# STM.net
KiCad netlist of a schematic drawn in Altium Designer
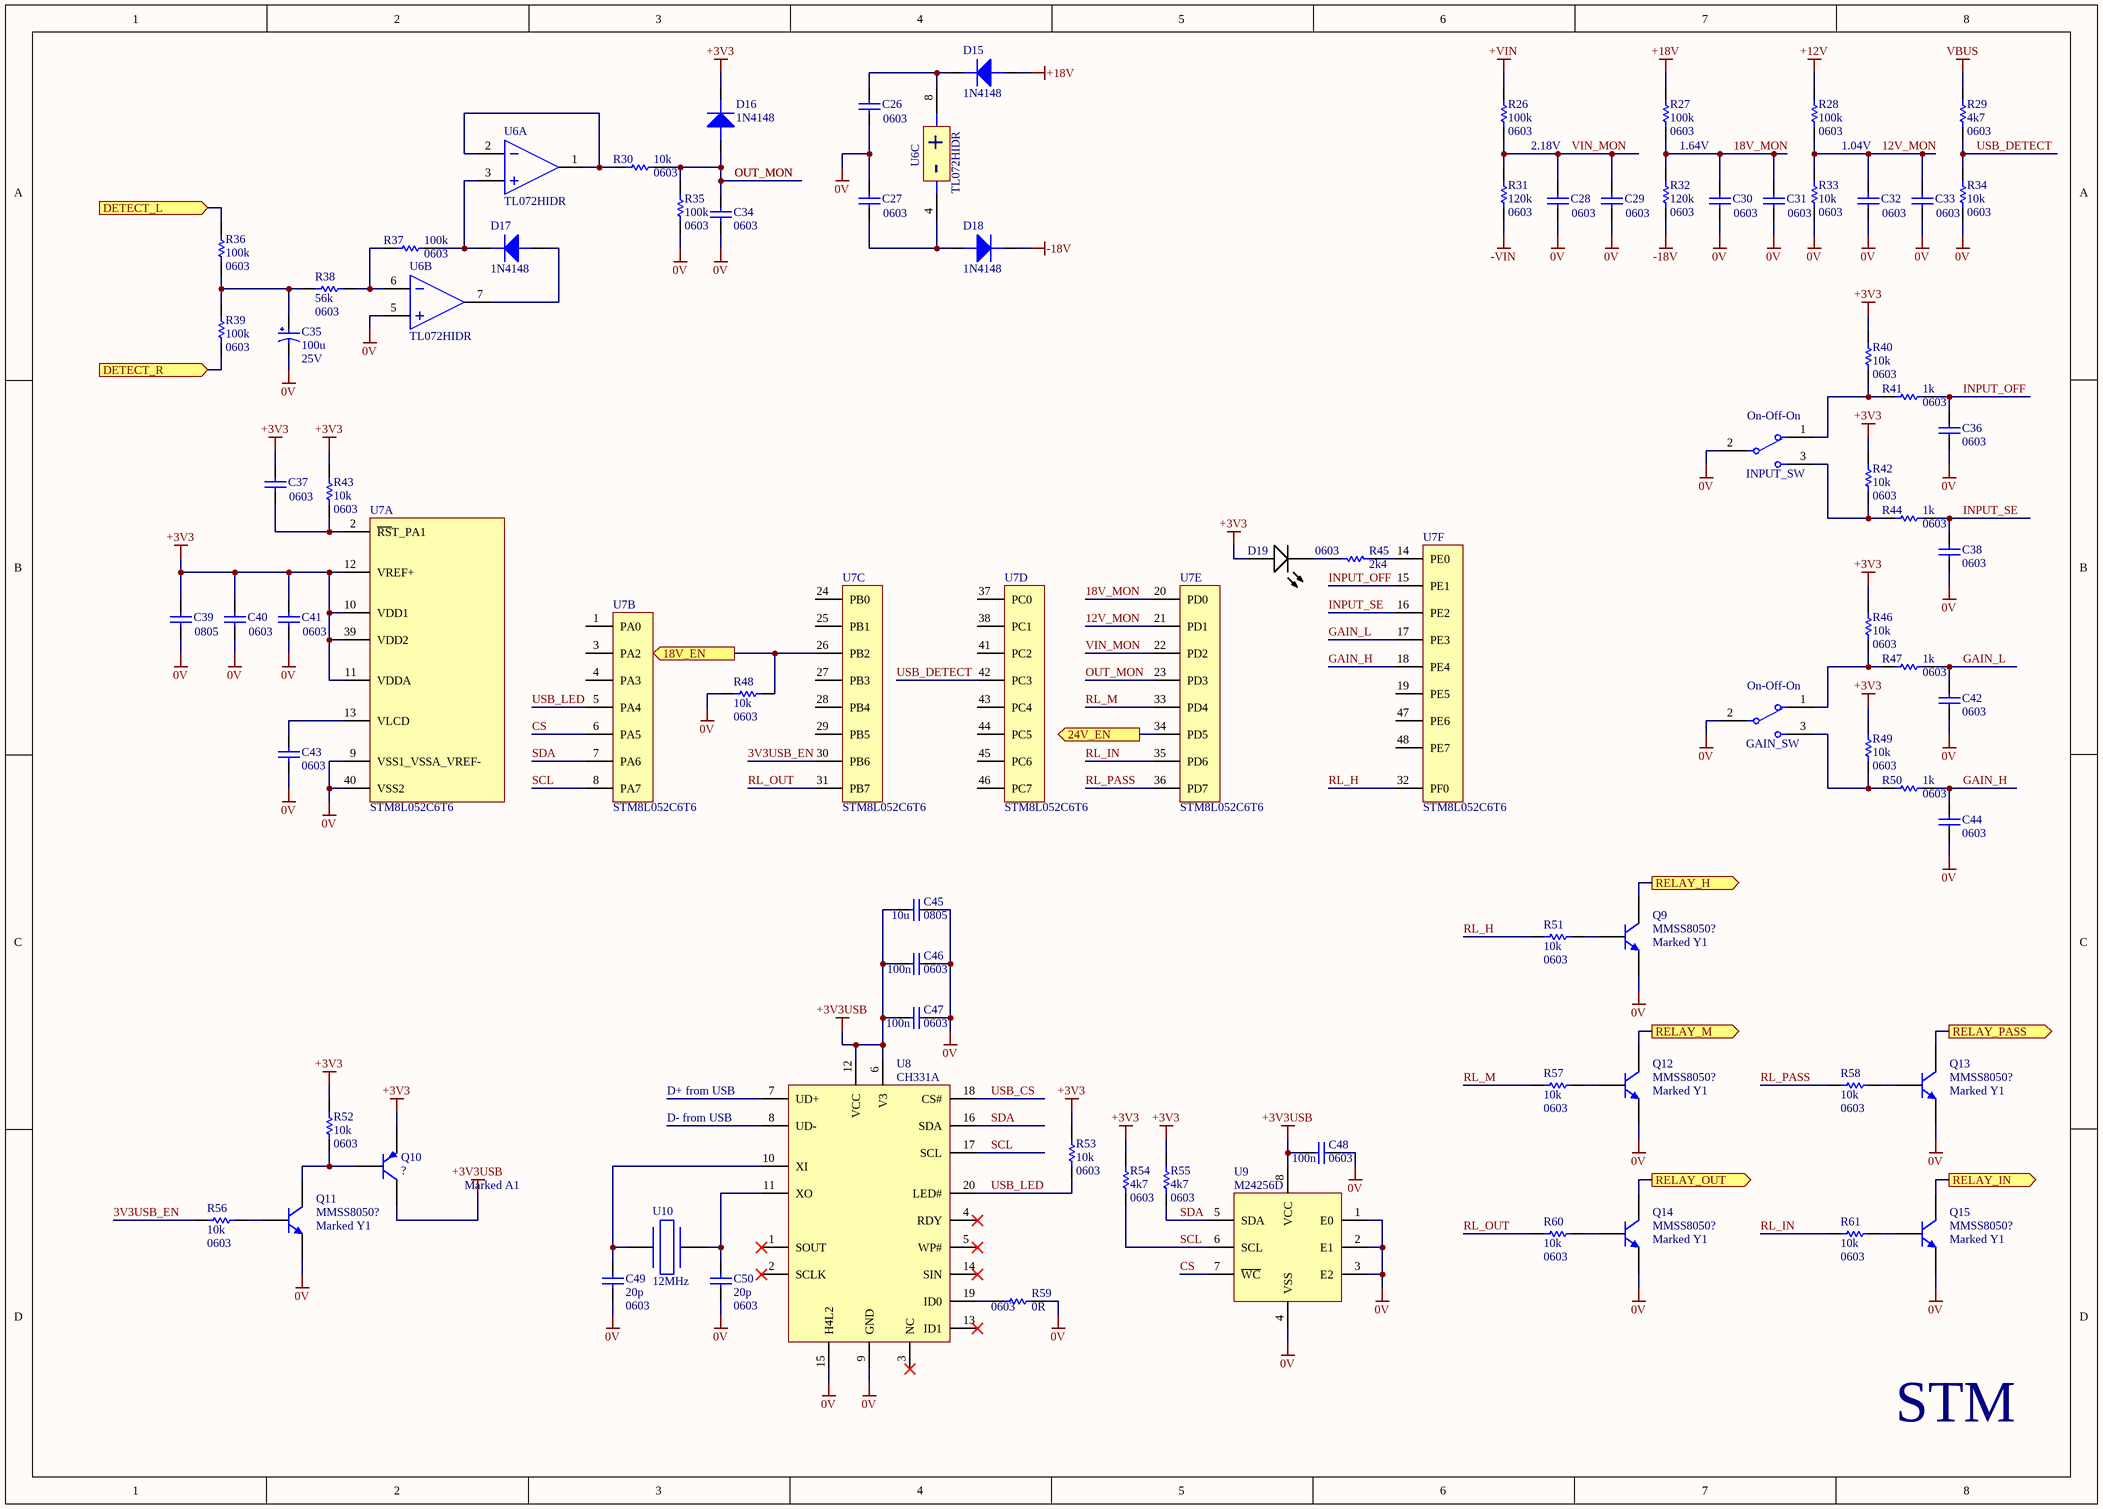
[diagram p0: STM.SchDoc]

(export (version "E")
  (design (tool "Eeschema 10.0.6"))
  (components
    (comp (ref "C26")
      (value "C_MLCC_0603")
      (footprint "CAPC1608X09N")
      (description "Generic MLCC 0603 Non Polarized Capacitor")
      (fields (field (name "MANUFACTURER") "Generic") (field (name "PACKAGE") "0603"))
      (libsource (lib "Topping_L50") (part "C_MLCC_0603"))
    )
    (comp (ref "C27")
      (value "C_MLCC_0603")
      (footprint "CAPC1608X09N")
      (description "Generic MLCC 0603 Non Polarized Capacitor")
      (fields (field (name "MANUFACTURER") "Generic") (field (name "PACKAGE") "0603"))
      (libsource (lib "Topping_L50") (part "C_MLCC_0603"))
    )
    (comp (ref "C28")
      (value "C_MLCC_0603")
      (footprint "CAPC1608X09N")
      (description "Generic MLCC 0603 Non Polarized Capacitor")
      (fields (field (name "MANUFACTURER") "Generic") (field (name "PACKAGE") "0603"))
      (libsource (lib "Topping_L50") (part "C_MLCC_0603"))
    )
    (comp (ref "C29")
      (value "C_MLCC_0603")
      (footprint "CAPC1608X09N")
      (description "Generic MLCC 0603 Non Polarized Capacitor")
      (fields (field (name "MANUFACTURER") "Generic") (field (name "PACKAGE") "0603"))
      (libsource (lib "Topping_L50") (part "C_MLCC_0603"))
    )
    (comp (ref "C30")
      (value "C_MLCC_0603")
      (footprint "CAPC1608X09N")
      (description "Generic MLCC 0603 Non Polarized Capacitor")
      (fields (field (name "MANUFACTURER") "Generic") (field (name "PACKAGE") "0603"))
      (libsource (lib "Topping_L50") (part "C_MLCC_0603"))
    )
    (comp (ref "C31")
      (value "C_MLCC_0603")
      (footprint "CAPC1608X09N")
      (description "Generic MLCC 0603 Non Polarized Capacitor")
      (fields (field (name "MANUFACTURER") "Generic") (field (name "PACKAGE") "0603"))
      (libsource (lib "Topping_L50") (part "C_MLCC_0603"))
    )
    (comp (ref "C32")
      (value "C_MLCC_0603")
      (footprint "CAPC1608X09N")
      (description "Generic MLCC 0603 Non Polarized Capacitor")
      (fields (field (name "MANUFACTURER") "Generic") (field (name "PACKAGE") "0603"))
      (libsource (lib "Topping_L50") (part "C_MLCC_0603"))
    )
    (comp (ref "C33")
      (value "C_MLCC_0603")
      (footprint "CAPC1608X09N")
      (description "Generic MLCC 0603 Non Polarized Capacitor")
      (fields (field (name "MANUFACTURER") "Generic") (field (name "PACKAGE") "0603"))
      (libsource (lib "Topping_L50") (part "C_MLCC_0603"))
    )
    (comp (ref "C34")
      (value "C_MLCC_0603")
      (footprint "CAPC1608X09N")
      (description "Generic MLCC 0603 Non Polarized Capacitor")
      (fields (field (name "MANUFACTURER") "Generic") (field (name "PACKAGE") "0603"))
      (libsource (lib "Topping_L50") (part "C_MLCC_0603"))
    )
    (comp (ref "C35")
      (value "100u")
      (footprint "CAPAE13X20")
      (description "Alum. Electrolytic Cap 2200µF 16V 13mm Radial WCAP-ATLL; Lifetime 7000h +105°C")
      (fields
        (field (name "MANUFACTURER") "Würth Elektronik")
        (field (name "TOLERANCE") "20%")
        (field (name "NOTES") "25V")
      )
      (libsource (lib "Topping_L50") (part "860160378038"))
    )
    (comp (ref "C36")
      (value "C_MLCC_0603")
      (footprint "CAPC1608X09N")
      (description "Generic MLCC 0603 Non Polarized Capacitor")
      (fields (field (name "MANUFACTURER") "Generic") (field (name "PACKAGE") "0603"))
      (libsource (lib "Topping_L50") (part "C_MLCC_0603"))
    )
    (comp (ref "C37")
      (value "C_MLCC_0603")
      (footprint "CAPC1608X09N")
      (description "Generic MLCC 0603 Non Polarized Capacitor")
      (fields (field (name "MANUFACTURER") "Generic") (field (name "PACKAGE") "0603"))
      (libsource (lib "Topping_L50") (part "C_MLCC_0603"))
    )
    (comp (ref "C38")
      (value "C_MLCC_0603")
      (footprint "CAPC1608X09N")
      (description "Generic MLCC 0603 Non Polarized Capacitor")
      (fields (field (name "MANUFACTURER") "Generic") (field (name "PACKAGE") "0603"))
      (libsource (lib "Topping_L50") (part "C_MLCC_0603"))
    )
    (comp (ref "C39")
      (value "C_MLCC_0805")
      (footprint "CAPC2012X14N")
      (description "Generic MLCC 0805 Non Polarized Capacitor")
      (fields (field (name "MANUFACTURER") "Generic") (field (name "PACKAGE") "0805"))
      (libsource (lib "Topping_L50") (part "C_MLCC_0805"))
    )
    (comp (ref "C40")
      (value "C_MLCC_0603")
      (footprint "CAPC1608X09N")
      (description "Generic MLCC 0603 Non Polarized Capacitor")
      (fields (field (name "MANUFACTURER") "Generic") (field (name "PACKAGE") "0603"))
      (libsource (lib "Topping_L50") (part "C_MLCC_0603"))
    )
    (comp (ref "C41")
      (value "C_MLCC_0603")
      (footprint "CAPC1608X09N")
      (description "Generic MLCC 0603 Non Polarized Capacitor")
      (fields (field (name "MANUFACTURER") "Generic") (field (name "PACKAGE") "0603"))
      (libsource (lib "Topping_L50") (part "C_MLCC_0603"))
    )
    (comp (ref "C42")
      (value "C_MLCC_0603")
      (footprint "CAPC1608X09N")
      (description "Generic MLCC 0603 Non Polarized Capacitor")
      (fields (field (name "MANUFACTURER") "Generic") (field (name "PACKAGE") "0603"))
      (libsource (lib "Topping_L50") (part "C_MLCC_0603"))
    )
    (comp (ref "C43")
      (value "C_MLCC_0603")
      (footprint "CAPC1608X09N")
      (description "Generic MLCC 0603 Non Polarized Capacitor")
      (fields (field (name "MANUFACTURER") "Generic") (field (name "PACKAGE") "0603"))
      (libsource (lib "Topping_L50") (part "C_MLCC_0603"))
    )
    (comp (ref "C44")
      (value "C_MLCC_0603")
      (footprint "CAPC1608X09N")
      (description "Generic MLCC 0603 Non Polarized Capacitor")
      (fields (field (name "MANUFACTURER") "Generic") (field (name "PACKAGE") "0603"))
      (libsource (lib "Topping_L50") (part "C_MLCC_0603"))
    )
    (comp (ref "C45")
      (value "10u")
      (footprint "CAPC2012X14N")
      (description "Generic MLCC 0805 Non Polarized Capacitor")
      (fields
        (field (name "MANUFACTURER") "Generic")
        (field (name "PACKAGE") "0805")
        (field (name "Comment") "C_MLCC_0805")
      )
      (libsource (lib "Topping_L50") (part "C_MLCC_0805"))
    )
    (comp (ref "C46")
      (value "100n")
      (footprint "CAPC1608X09N")
      (description "Generic MLCC 0603 Non Polarized Capacitor")
      (fields
        (field (name "MANUFACTURER") "Generic")
        (field (name "PACKAGE") "0603")
        (field (name "Comment") "C_MLCC_0603")
      )
      (libsource (lib "Topping_L50") (part "C_MLCC_0603"))
    )
    (comp (ref "C47")
      (value "100n")
      (footprint "CAPC1608X09N")
      (description "Generic MLCC 0603 Non Polarized Capacitor")
      (fields
        (field (name "MANUFACTURER") "Generic")
        (field (name "PACKAGE") "0603")
        (field (name "Comment") "C_MLCC_0603")
      )
      (libsource (lib "Topping_L50") (part "C_MLCC_0603"))
    )
    (comp (ref "C48")
      (value "100n")
      (footprint "CAPC1608X09N")
      (description "Generic MLCC 0603 Non Polarized Capacitor")
      (fields
        (field (name "MANUFACTURER") "Generic")
        (field (name "PACKAGE") "0603")
        (field (name "Comment") "C_MLCC_0603")
      )
      (libsource (lib "Topping_L50") (part "C_MLCC_0603"))
    )
    (comp (ref "C49")
      (value "20p")
      (footprint "CAPC1608X09N")
      (description "Generic MLCC 0603 Non Polarized Capacitor")
      (fields
        (field (name "MANUFACTURER") "Generic")
        (field (name "PACKAGE") "0603")
        (field (name "Comment") "C_MLCC_0603")
      )
      (libsource (lib "Topping_L50") (part "C_MLCC_0603"))
    )
    (comp (ref "C50")
      (value "20p")
      (footprint "CAPC1608X09N")
      (description "Generic MLCC 0603 Non Polarized Capacitor")
      (fields
        (field (name "MANUFACTURER") "Generic")
        (field (name "PACKAGE") "0603")
        (field (name "Comment") "C_MLCC_0603")
      )
      (libsource (lib "Topping_L50") (part "C_MLCC_0603"))
    )
    (comp (ref "D15")
      (value "1N4148")
      (description "Generic small signal diode")
      (fields (field (name "MANUFACTURER") "Generic") (field (name "MANUFACTURER PART NUMBER") "BAT48ZFILM"))
      (libsource (lib "Topping_L50") (part "1N4148"))
    )
    (comp (ref "D16")
      (value "1N4148")
      (description "Generic small signal diode")
      (fields (field (name "MANUFACTURER") "Generic") (field (name "MANUFACTURER PART NUMBER") "BAT48ZFILM"))
      (libsource (lib "Topping_L50") (part "1N4148"))
    )
    (comp (ref "D17")
      (value "1N4148")
      (description "Generic small signal diode")
      (fields (field (name "MANUFACTURER") "Generic") (field (name "MANUFACTURER PART NUMBER") "BAT48ZFILM"))
      (libsource (lib "Topping_L50") (part "1N4148"))
    )
    (comp (ref "D18")
      (value "1N4148")
      (description "Generic small signal diode")
      (fields (field (name "MANUFACTURER") "Generic") (field (name "MANUFACTURER PART NUMBER") "BAT48ZFILM"))
      (libsource (lib "Topping_L50") (part "1N4148"))
    )
    (comp (ref "D19")
      (value "LED_TH_3mm_RED")
      (description "Generic Through Hole 3mm Red Led")
      (fields (field (name "MANUFACTURER") "Generic"))
      (libsource (lib "Topping_L50") (part "LED_TH_3mm_RED"))
    )
    (comp (ref "GAIN_SW")
      (value "On-Off-On")
      (description "Mini Toggle Switch 1M Series SPDT ON-ON Short Lever PC Through-Hole")
      (fields (field (name "MANUFACTURER") "Dailywell") (field (name "Comment") "1MS1T2B1M2QES"))
      (libsource (lib "Topping_L50") (part "1MS1T2B1M2QES"))
    )
    (comp (ref "INPUT_SW")
      (value "On-Off-On")
      (description "Mini Toggle Switch 1M Series SPDT ON-ON Short Lever PC Through-Hole")
      (fields (field (name "MANUFACTURER") "Dailywell") (field (name "Comment") "1MS1T2B1M2QES"))
      (libsource (lib "Topping_L50") (part "1MS1T2B1M2QES"))
    )
    (comp (ref "Q9")
      (value "MMSS8050?")
      (footprint "SOT95P230X110-3N")
      (description "NPN General-Purpose\r\nAmplifier")
      (fields (field (name "MANUFACTURER") "On Semi") (field (name "MANUFACTURER PART NUMBER") "MMBT3904VL"))
      (libsource (lib "Topping_L50") (part "MMBT5551"))
    )
    (comp (ref "Q10")
      (value "?")
      (footprint "SOT95P230X110-3N")
      (description "PNP Epitaxial Silicon Transistor")
      (fields (field (name "MANUFACTURER") "MCC") (field (name "MANUFACTURER PART NUMBER") "MMBT3904VL"))
      (libsource (lib "Topping_L50") (part "MMBT5401"))
    )
    (comp (ref "Q11")
      (value "MMSS8050?")
      (footprint "SOT95P230X110-3N")
      (description "NPN General-Purpose\r\nAmplifier")
      (fields (field (name "MANUFACTURER") "On Semi") (field (name "MANUFACTURER PART NUMBER") "MMBT3904VL"))
      (libsource (lib "Topping_L50") (part "MMBT5551"))
    )
    (comp (ref "Q12")
      (value "MMSS8050?")
      (footprint "SOT95P230X110-3N")
      (description "NPN General-Purpose\r\nAmplifier")
      (fields (field (name "MANUFACTURER") "On Semi") (field (name "MANUFACTURER PART NUMBER") "MMBT3904VL"))
      (libsource (lib "Topping_L50") (part "MMBT5551"))
    )
    (comp (ref "Q13")
      (value "MMSS8050?")
      (footprint "SOT95P230X110-3N")
      (description "NPN General-Purpose\r\nAmplifier")
      (fields (field (name "MANUFACTURER") "On Semi") (field (name "MANUFACTURER PART NUMBER") "MMBT3904VL"))
      (libsource (lib "Topping_L50") (part "MMBT5551"))
    )
    (comp (ref "Q14")
      (value "MMSS8050?")
      (footprint "SOT95P230X110-3N")
      (description "NPN General-Purpose\r\nAmplifier")
      (fields (field (name "MANUFACTURER") "On Semi") (field (name "MANUFACTURER PART NUMBER") "MMBT3904VL"))
      (libsource (lib "Topping_L50") (part "MMBT5551"))
    )
    (comp (ref "Q15")
      (value "MMSS8050?")
      (footprint "SOT95P230X110-3N")
      (description "NPN General-Purpose\r\nAmplifier")
      (fields (field (name "MANUFACTURER") "On Semi") (field (name "MANUFACTURER PART NUMBER") "MMBT3904VL"))
      (libsource (lib "Topping_L50") (part "MMBT5551"))
    )
    (comp (ref "R26")
      (value "100k")
      (footprint "RESC1608X06N")
      (description "Generic 0603 Single Resistor")
      (fields
        (field (name "MANUFACTURER") "Generic")
        (field (name "PACKAGE") "0603")
        (field (name "Comment") "R")
      )
      (libsource (lib "Topping_L50") (part "R_0603"))
    )
    (comp (ref "R27")
      (value "100k")
      (footprint "RESC1608X06N")
      (description "Generic 0603 Single Resistor")
      (fields
        (field (name "MANUFACTURER") "Generic")
        (field (name "PACKAGE") "0603")
        (field (name "Comment") "R")
      )
      (libsource (lib "Topping_L50") (part "R_0603"))
    )
    (comp (ref "R28")
      (value "100k")
      (footprint "RESC1608X06N")
      (description "Generic 0603 Single Resistor")
      (fields
        (field (name "MANUFACTURER") "Generic")
        (field (name "PACKAGE") "0603")
        (field (name "Comment") "R")
      )
      (libsource (lib "Topping_L50") (part "R_0603"))
    )
    (comp (ref "R29")
      (value "4k7")
      (footprint "RESC1608X06N")
      (description "Generic 0603 Single Resistor")
      (fields
        (field (name "MANUFACTURER") "Generic")
        (field (name "PACKAGE") "0603")
        (field (name "Comment") "R")
      )
      (libsource (lib "Topping_L50") (part "R_0603"))
    )
    (comp (ref "R30")
      (value "10k")
      (footprint "RESC1608X06N")
      (description "Generic 0603 Single Resistor")
      (fields
        (field (name "MANUFACTURER") "Generic")
        (field (name "PACKAGE") "0603")
        (field (name "Comment") "R")
      )
      (libsource (lib "Topping_L50") (part "R_0603"))
    )
    (comp (ref "R31")
      (value "120k")
      (footprint "RESC1608X06N")
      (description "Generic 0603 Single Resistor")
      (fields
        (field (name "MANUFACTURER") "Generic")
        (field (name "PACKAGE") "0603")
        (field (name "Comment") "R")
      )
      (libsource (lib "Topping_L50") (part "R_0603"))
    )
    (comp (ref "R32")
      (value "120k")
      (footprint "RESC1608X06N")
      (description "Generic 0603 Single Resistor")
      (fields
        (field (name "MANUFACTURER") "Generic")
        (field (name "PACKAGE") "0603")
        (field (name "Comment") "R")
      )
      (libsource (lib "Topping_L50") (part "R_0603"))
    )
    (comp (ref "R33")
      (value "10k")
      (footprint "RESC1608X06N")
      (description "Generic 0603 Single Resistor")
      (fields
        (field (name "MANUFACTURER") "Generic")
        (field (name "PACKAGE") "0603")
        (field (name "Comment") "R")
      )
      (libsource (lib "Topping_L50") (part "R_0603"))
    )
    (comp (ref "R34")
      (value "10k")
      (footprint "RESC1608X06N")
      (description "Generic 0603 Single Resistor")
      (fields
        (field (name "MANUFACTURER") "Generic")
        (field (name "PACKAGE") "0603")
        (field (name "Comment") "R")
      )
      (libsource (lib "Topping_L50") (part "R_0603"))
    )
    (comp (ref "R35")
      (value "100k")
      (footprint "RESC1608X06N")
      (description "Generic 0603 Single Resistor")
      (fields
        (field (name "MANUFACTURER") "Generic")
        (field (name "PACKAGE") "0603")
        (field (name "Comment") "R")
      )
      (libsource (lib "Topping_L50") (part "R_0603"))
    )
    (comp (ref "R36")
      (value "100k")
      (footprint "RESC1608X06N")
      (description "Generic 0603 Single Resistor")
      (fields
        (field (name "MANUFACTURER") "Generic")
        (field (name "PACKAGE") "0603")
        (field (name "Comment") "R")
      )
      (libsource (lib "Topping_L50") (part "R_0603"))
    )
    (comp (ref "R37")
      (value "100k")
      (footprint "RESC1608X06N")
      (description "Generic 0603 Single Resistor")
      (fields
        (field (name "MANUFACTURER") "Generic")
        (field (name "PACKAGE") "0603")
        (field (name "Comment") "R")
      )
      (libsource (lib "Topping_L50") (part "R_0603"))
    )
    (comp (ref "R38")
      (value "56k")
      (footprint "RESC1608X06N")
      (description "Generic 0603 Single Resistor")
      (fields
        (field (name "MANUFACTURER") "Generic")
        (field (name "PACKAGE") "0603")
        (field (name "Comment") "R")
      )
      (libsource (lib "Topping_L50") (part "R_0603"))
    )
    (comp (ref "R39")
      (value "100k")
      (footprint "RESC1608X06N")
      (description "Generic 0603 Single Resistor")
      (fields
        (field (name "MANUFACTURER") "Generic")
        (field (name "PACKAGE") "0603")
        (field (name "Comment") "R")
      )
      (libsource (lib "Topping_L50") (part "R_0603"))
    )
    (comp (ref "R40")
      (value "10k")
      (footprint "RESC1608X06N")
      (description "Generic 0603 Single Resistor")
      (fields
        (field (name "MANUFACTURER") "Generic")
        (field (name "PACKAGE") "0603")
        (field (name "Comment") "R")
      )
      (libsource (lib "Topping_L50") (part "R_0603"))
    )
    (comp (ref "R41")
      (value "1k")
      (footprint "RESC1608X06N")
      (description "Generic 0603 Single Resistor")
      (fields
        (field (name "MANUFACTURER") "Generic")
        (field (name "PACKAGE") "0603")
        (field (name "Comment") "R")
      )
      (libsource (lib "Topping_L50") (part "R_0603"))
    )
    (comp (ref "R42")
      (value "10k")
      (footprint "RESC1608X06N")
      (description "Generic 0603 Single Resistor")
      (fields
        (field (name "MANUFACTURER") "Generic")
        (field (name "PACKAGE") "0603")
        (field (name "Comment") "R")
      )
      (libsource (lib "Topping_L50") (part "R_0603"))
    )
    (comp (ref "R43")
      (value "10k")
      (footprint "RESC1608X06N")
      (description "Generic 0603 Single Resistor")
      (fields
        (field (name "MANUFACTURER") "Generic")
        (field (name "PACKAGE") "0603")
        (field (name "Comment") "R")
      )
      (libsource (lib "Topping_L50") (part "R_0603"))
    )
    (comp (ref "R44")
      (value "1k")
      (footprint "RESC1608X06N")
      (description "Generic 0603 Single Resistor")
      (fields
        (field (name "MANUFACTURER") "Generic")
        (field (name "PACKAGE") "0603")
        (field (name "Comment") "R")
      )
      (libsource (lib "Topping_L50") (part "R_0603"))
    )
    (comp (ref "R45")
      (value "2k4")
      (footprint "RESC1608X06N")
      (description "Generic 0603 Single Resistor")
      (fields
        (field (name "MANUFACTURER") "Generic")
        (field (name "PACKAGE") "0603")
        (field (name "Comment") "R")
      )
      (libsource (lib "Topping_L50") (part "R_0603"))
    )
    (comp (ref "R46")
      (value "10k")
      (footprint "RESC1608X06N")
      (description "Generic 0603 Single Resistor")
      (fields
        (field (name "MANUFACTURER") "Generic")
        (field (name "PACKAGE") "0603")
        (field (name "Comment") "R")
      )
      (libsource (lib "Topping_L50") (part "R_0603"))
    )
    (comp (ref "R47")
      (value "1k")
      (footprint "RESC1608X06N")
      (description "Generic 0603 Single Resistor")
      (fields
        (field (name "MANUFACTURER") "Generic")
        (field (name "PACKAGE") "0603")
        (field (name "Comment") "R")
      )
      (libsource (lib "Topping_L50") (part "R_0603"))
    )
    (comp (ref "R48")
      (value "10k")
      (footprint "RESC1608X06N")
      (description "Generic 0603 Single Resistor")
      (fields
        (field (name "MANUFACTURER") "Generic")
        (field (name "PACKAGE") "0603")
        (field (name "Comment") "R")
      )
      (libsource (lib "Topping_L50") (part "R_0603"))
    )
    (comp (ref "R49")
      (value "10k")
      (footprint "RESC1608X06N")
      (description "Generic 0603 Single Resistor")
      (fields
        (field (name "MANUFACTURER") "Generic")
        (field (name "PACKAGE") "0603")
        (field (name "Comment") "R")
      )
      (libsource (lib "Topping_L50") (part "R_0603"))
    )
    (comp (ref "R50")
      (value "1k")
      (footprint "RESC1608X06N")
      (description "Generic 0603 Single Resistor")
      (fields
        (field (name "MANUFACTURER") "Generic")
        (field (name "PACKAGE") "0603")
        (field (name "Comment") "R")
      )
      (libsource (lib "Topping_L50") (part "R_0603"))
    )
    (comp (ref "R51")
      (value "10k")
      (footprint "RESC1608X06N")
      (description "Generic 0603 Single Resistor")
      (fields
        (field (name "MANUFACTURER") "Generic")
        (field (name "PACKAGE") "0603")
        (field (name "Comment") "R")
      )
      (libsource (lib "Topping_L50") (part "R_0603"))
    )
    (comp (ref "R52")
      (value "10k")
      (footprint "RESC1608X06N")
      (description "Generic 0603 Single Resistor")
      (fields
        (field (name "MANUFACTURER") "Generic")
        (field (name "PACKAGE") "0603")
        (field (name "Comment") "R")
      )
      (libsource (lib "Topping_L50") (part "R_0603"))
    )
    (comp (ref "R53")
      (value "10k")
      (footprint "RESC1608X06N")
      (description "Generic 0603 Single Resistor")
      (fields
        (field (name "MANUFACTURER") "Generic")
        (field (name "PACKAGE") "0603")
        (field (name "Comment") "R")
      )
      (libsource (lib "Topping_L50") (part "R_0603"))
    )
    (comp (ref "R54")
      (value "4k7")
      (footprint "RESC1608X06N")
      (description "Generic 0603 Single Resistor")
      (fields
        (field (name "MANUFACTURER") "Generic")
        (field (name "PACKAGE") "0603")
        (field (name "Comment") "R")
      )
      (libsource (lib "Topping_L50") (part "R_0603"))
    )
    (comp (ref "R55")
      (value "4k7")
      (footprint "RESC1608X06N")
      (description "Generic 0603 Single Resistor")
      (fields
        (field (name "MANUFACTURER") "Generic")
        (field (name "PACKAGE") "0603")
        (field (name "Comment") "R")
      )
      (libsource (lib "Topping_L50") (part "R_0603"))
    )
    (comp (ref "R56")
      (value "10k")
      (footprint "RESC1608X06N")
      (description "Generic 0603 Single Resistor")
      (fields
        (field (name "MANUFACTURER") "Generic")
        (field (name "PACKAGE") "0603")
        (field (name "Comment") "R")
      )
      (libsource (lib "Topping_L50") (part "R_0603"))
    )
    (comp (ref "R57")
      (value "10k")
      (footprint "RESC1608X06N")
      (description "Generic 0603 Single Resistor")
      (fields
        (field (name "MANUFACTURER") "Generic")
        (field (name "PACKAGE") "0603")
        (field (name "Comment") "R")
      )
      (libsource (lib "Topping_L50") (part "R_0603"))
    )
    (comp (ref "R58")
      (value "10k")
      (footprint "RESC1608X06N")
      (description "Generic 0603 Single Resistor")
      (fields
        (field (name "MANUFACTURER") "Generic")
        (field (name "PACKAGE") "0603")
        (field (name "Comment") "R")
      )
      (libsource (lib "Topping_L50") (part "R_0603"))
    )
    (comp (ref "R59")
      (value "0R")
      (footprint "RESC1608X06N")
      (description "Generic 0603 Single Resistor")
      (fields
        (field (name "MANUFACTURER") "Generic")
        (field (name "PACKAGE") "0603")
        (field (name "Comment") "R")
      )
      (libsource (lib "Topping_L50") (part "R_0603"))
    )
    (comp (ref "R60")
      (value "10k")
      (footprint "RESC1608X06N")
      (description "Generic 0603 Single Resistor")
      (fields
        (field (name "MANUFACTURER") "Generic")
        (field (name "PACKAGE") "0603")
        (field (name "Comment") "R")
      )
      (libsource (lib "Topping_L50") (part "R_0603"))
    )
    (comp (ref "R61")
      (value "10k")
      (footprint "RESC1608X06N")
      (description "Generic 0603 Single Resistor")
      (fields
        (field (name "MANUFACTURER") "Generic")
        (field (name "PACKAGE") "0603")
        (field (name "Comment") "R")
      )
      (libsource (lib "Topping_L50") (part "R_0603"))
    )
    (comp (ref "U6")
      (value "TL072HIDR")
      (footprint "SOIC127P600X175-8L")
      (description "Operational Amplifiers - Op Amps Dual Low Noise Op Amp")
      (fields (field (name "MANUFACTURER") "Texas Instruments"))
      (libsource (lib "Topping_L50") (part "TL072HIDR"))
    )
    (comp (ref "U7")
      (value "STM8L052C6T6")
      (footprint "CQFP50P900X900X160-48N")
      (fields (field (name "MANUFACTURER") "ST Microelectronics"))
      (libsource (lib "Topping_L50") (part "STM8L052C6T6"))
    )
    (comp (ref "U8")
      (value "CH331A")
      (footprint "TSOP65P640X120-20N")
      (description "USB 2.0 SSOP-20-208mil USB Converters ROHS")
      (fields (field (name "MANUFACTURER") "WCH"))
      (libsource (lib "Topping_L50") (part "CH331A"))
    )
    (comp (ref "U9")
      (value "M24256D")
      (footprint "SOIC127P600X175-8L")
      (description "256-Kbit serial I²C bus EEPROM")
      (fields (field (name "MANUFACTURER") "ST Microelectronics"))
      (libsource (lib "Topping_L50") (part "M24256D"))
    )
    (comp (ref "U10")
      (value "12MHz")
      (description "Generic Xtal")
      (libsource (lib "Topping_L50") (part "Xtal"))
    )
  )
  (nets
    (net (code "1") (name "+3V3") (class "Default")
      (node (ref "C37") (pin "1") (pinfunction "1_1") (pintype "passive"))
      (node (ref "C39") (pin "2") (pinfunction "2_2") (pintype "passive"))
      (node (ref "C40") (pin "1") (pinfunction "1_1") (pintype "passive"))
      (node (ref "C41") (pin "1") (pinfunction "1_1") (pintype "passive"))
      (node (ref "D16") (pin "K") (pinfunction "K_K") (pintype "passive"))
      (node (ref "D19") (pin "A") (pinfunction "A_A") (pintype "passive"))
      (node (ref "Q10") (pin "E") (pinfunction "E_E") (pintype "passive"))
      (node (ref "R40") (pin "1") (pinfunction "1_1") (pintype "passive"))
      (node (ref "R42") (pin "2") (pinfunction "2_2") (pintype "passive"))
      (node (ref "R43") (pin "2") (pinfunction "2_2") (pintype "passive"))
      (node (ref "R46") (pin "1") (pinfunction "1_1") (pintype "passive"))
      (node (ref "R49") (pin "2") (pinfunction "2_2") (pintype "passive"))
      (node (ref "R52") (pin "2") (pinfunction "2_2") (pintype "passive"))
      (node (ref "R53") (pin "2") (pinfunction "2_2") (pintype "passive"))
      (node (ref "R54") (pin "2") (pinfunction "2_2") (pintype "passive"))
      (node (ref "R55") (pin "2") (pinfunction "2_2") (pintype "passive"))
      (node (ref "U7") (pin "10") (pinfunction "VDD1_10") (pintype "passive"))
      (node (ref "U7") (pin "11") (pinfunction "VDDA_11") (pintype "passive"))
      (node (ref "U7") (pin "12") (pinfunction "VREF+_12") (pintype "passive"))
      (node (ref "U7") (pin "39") (pinfunction "VDD2_39") (pintype "passive"))
    )
    (net (code "2") (name "+3V3USB") (class "Default")
      (node (ref "C45") (pin "2") (pinfunction "2_2") (pintype "passive"))
      (node (ref "C46") (pin "2") (pinfunction "2_2") (pintype "passive"))
      (node (ref "C47") (pin "2") (pinfunction "2_2") (pintype "passive"))
      (node (ref "C48") (pin "2") (pinfunction "2_2") (pintype "passive"))
      (node (ref "Q10") (pin "C") (pinfunction "C_C") (pintype "passive"))
      (node (ref "U8") (pin "12") (pinfunction "VCC_12") (pintype "passive"))
      (node (ref "U8") (pin "6") (pinfunction "V3_6") (pintype "passive"))
      (node (ref "U9") (pin "8") (pinfunction "VCC_8") (pintype "passive"))
    )
    (net (code "3") (name "+12V") (class "Default")
      (node (ref "R28") (pin "2") (pinfunction "2_2") (pintype "passive"))
    )
    (net (code "4") (name "+18V") (class "Default")
      (node (ref "D15") (pin "A") (pinfunction "A_A") (pintype "passive"))
      (node (ref "R27") (pin "2") (pinfunction "2_2") (pintype "passive"))
    )
    (net (code "5") (name "+VIN") (class "Default")
      (node (ref "R26") (pin "2") (pinfunction "2_2") (pintype "passive"))
    )
    (net (code "6") (name "-18V") (class "Default")
      (node (ref "D18") (pin "K") (pinfunction "K_K") (pintype "passive"))
      (node (ref "R32") (pin "1") (pinfunction "1_1") (pintype "passive"))
    )
    (net (code "7") (name "-VIN") (class "Default")
      (node (ref "R31") (pin "1") (pinfunction "1_1") (pintype "passive"))
    )
    (net (code "8") (name "/3V3USB_EN") (class "Default")
      (node (ref "R56") (pin "1") (pinfunction "1_1") (pintype "passive"))
      (node (ref "U7") (pin "30") (pinfunction "PB6_30") (pintype "passive"))
    )
    (net (code "9") (name "/12V_MON") (class "Default")
      (node (ref "C32") (pin "2") (pinfunction "2_2") (pintype "passive"))
      (node (ref "C33") (pin "2") (pinfunction "2_2") (pintype "passive"))
      (node (ref "R28") (pin "1") (pinfunction "1_1") (pintype "passive"))
      (node (ref "R33") (pin "2") (pinfunction "2_2") (pintype "passive"))
      (node (ref "U7") (pin "21") (pinfunction "PD1_21") (pintype "passive"))
    )
    (net (code "10") (name "/18V_EN") (class "Default")
      (node (ref "R48") (pin "2") (pinfunction "2_2") (pintype "passive"))
      (node (ref "U7") (pin "26") (pinfunction "PB2_26") (pintype "passive"))
    )
    (net (code "11") (name "/18V_MON") (class "Default")
      (node (ref "C30") (pin "2") (pinfunction "2_2") (pintype "passive"))
      (node (ref "C31") (pin "2") (pinfunction "2_2") (pintype "passive"))
      (node (ref "R27") (pin "1") (pinfunction "1_1") (pintype "passive"))
      (node (ref "R32") (pin "2") (pinfunction "2_2") (pintype "passive"))
      (node (ref "U7") (pin "20") (pinfunction "PD0_20") (pintype "passive"))
    )
    (net (code "12") (name "/24V_EN") (class "Default")
      (node (ref "U7") (pin "34") (pinfunction "PD5_34") (pintype "passive"))
    )
    (net (code "13") (name "/CS") (class "Default")
      (node (ref "U7") (pin "6") (pinfunction "PA5_6") (pintype "passive"))
      (node (ref "U9") (pin "7") (pinfunction "~{WC}_7") (pintype "passive"))
    )
    (net (code "14") (name "/DETECT_L") (class "Default")
      (node (ref "R36") (pin "1") (pinfunction "1_1") (pintype "passive"))
    )
    (net (code "15") (name "/DETECT_R") (class "Default")
      (node (ref "R39") (pin "2") (pinfunction "2_2") (pintype "passive"))
    )
    (net (code "16") (name "/GAIN_H") (class "Default")
      (node (ref "C44") (pin "2") (pinfunction "2_2") (pintype "passive"))
      (node (ref "R50") (pin "2") (pinfunction "2_2") (pintype "passive"))
      (node (ref "U7") (pin "18") (pinfunction "PE4_18") (pintype "passive"))
    )
    (net (code "17") (name "/GAIN_L") (class "Default")
      (node (ref "C42") (pin "2") (pinfunction "2_2") (pintype "passive"))
      (node (ref "R47") (pin "2") (pinfunction "2_2") (pintype "passive"))
      (node (ref "U7") (pin "17") (pinfunction "PE3_17") (pintype "passive"))
    )
    (net (code "18") (name "/INPUT_OFF") (class "Default")
      (node (ref "C36") (pin "2") (pinfunction "2_2") (pintype "passive"))
      (node (ref "R41") (pin "2") (pinfunction "2_2") (pintype "passive"))
      (node (ref "U7") (pin "15") (pinfunction "PE1_15") (pintype "passive"))
    )
    (net (code "19") (name "/INPUT_SE") (class "Default")
      (node (ref "C38") (pin "2") (pinfunction "2_2") (pintype "passive"))
      (node (ref "R44") (pin "2") (pinfunction "2_2") (pintype "passive"))
      (node (ref "U7") (pin "16") (pinfunction "PE2_16") (pintype "passive"))
    )
    (net (code "20") (name "/OUT_MON") (class "Default")
      (node (ref "C34") (pin "2") (pinfunction "2_2") (pintype "passive"))
      (node (ref "D16") (pin "A") (pinfunction "A_A") (pintype "passive"))
      (node (ref "R30") (pin "2") (pinfunction "2_2") (pintype "passive"))
      (node (ref "R35") (pin "2") (pinfunction "2_2") (pintype "passive"))
      (node (ref "U7") (pin "23") (pinfunction "PD3_23") (pintype "passive"))
    )
    (net (code "21") (name "/RELAY_H") (class "Default")
      (node (ref "Q9") (pin "C") (pinfunction "C_C") (pintype "passive"))
    )
    (net (code "22") (name "/RELAY_IN") (class "Default")
      (node (ref "Q15") (pin "C") (pinfunction "C_C") (pintype "passive"))
    )
    (net (code "23") (name "/RELAY_M") (class "Default")
      (node (ref "Q12") (pin "C") (pinfunction "C_C") (pintype "passive"))
    )
    (net (code "24") (name "/RELAY_OUT") (class "Default")
      (node (ref "Q14") (pin "C") (pinfunction "C_C") (pintype "passive"))
    )
    (net (code "25") (name "/RELAY_PASS") (class "Default")
      (node (ref "Q13") (pin "C") (pinfunction "C_C") (pintype "passive"))
    )
    (net (code "26") (name "/RL_H") (class "Default")
      (node (ref "R51") (pin "1") (pinfunction "1_1") (pintype "passive"))
      (node (ref "U7") (pin "32") (pinfunction "PF0_32") (pintype "passive"))
    )
    (net (code "27") (name "/RL_IN") (class "Default")
      (node (ref "R61") (pin "1") (pinfunction "1_1") (pintype "passive"))
      (node (ref "U7") (pin "35") (pinfunction "PD6_35") (pintype "passive"))
    )
    (net (code "28") (name "/RL_M") (class "Default")
      (node (ref "R57") (pin "1") (pinfunction "1_1") (pintype "passive"))
      (node (ref "U7") (pin "33") (pinfunction "PD4_33") (pintype "passive"))
    )
    (net (code "29") (name "/RL_OUT") (class "Default")
      (node (ref "R60") (pin "1") (pinfunction "1_1") (pintype "passive"))
      (node (ref "U7") (pin "31") (pinfunction "PB7_31") (pintype "passive"))
    )
    (net (code "30") (name "/RL_PASS") (class "Default")
      (node (ref "R58") (pin "1") (pinfunction "1_1") (pintype "passive"))
      (node (ref "U7") (pin "36") (pinfunction "PD7_36") (pintype "passive"))
    )
    (net (code "31") (name "/SCL") (class "Default")
      (node (ref "R54") (pin "1") (pinfunction "1_1") (pintype "passive"))
      (node (ref "U7") (pin "8") (pinfunction "PA7_8") (pintype "passive"))
      (node (ref "U8") (pin "17") (pinfunction "SCL_17") (pintype "passive"))
      (node (ref "U9") (pin "6") (pinfunction "SCL_6") (pintype "passive"))
    )
    (net (code "32") (name "/SDA") (class "Default")
      (node (ref "R55") (pin "1") (pinfunction "1_1") (pintype "passive"))
      (node (ref "U7") (pin "7") (pinfunction "PA6_7") (pintype "passive"))
      (node (ref "U8") (pin "16") (pinfunction "SDA_16") (pintype "passive"))
      (node (ref "U9") (pin "5") (pinfunction "SDA_5") (pintype "passive"))
    )
    (net (code "33") (name "/USB_CS") (class "Default")
      (node (ref "U8") (pin "18") (pinfunction "CS#_18") (pintype "passive"))
    )
    (net (code "34") (name "/USB_DETECT") (class "Default")
      (node (ref "R29") (pin "1") (pinfunction "1_1") (pintype "passive"))
      (node (ref "R34") (pin "2") (pinfunction "2_2") (pintype "passive"))
      (node (ref "U7") (pin "42") (pinfunction "PC3_42") (pintype "passive"))
    )
    (net (code "35") (name "/USB_LED") (class "Default")
      (node (ref "R53") (pin "1") (pinfunction "1_1") (pintype "passive"))
      (node (ref "U7") (pin "5") (pinfunction "PA4_5") (pintype "passive"))
      (node (ref "U8") (pin "20") (pinfunction "LED#_20") (pintype "passive"))
    )
    (net (code "36") (name "/VIN_MON") (class "Default")
      (node (ref "C28") (pin "2") (pinfunction "2_2") (pintype "passive"))
      (node (ref "C29") (pin "2") (pinfunction "2_2") (pintype "passive"))
      (node (ref "R26") (pin "1") (pinfunction "1_1") (pintype "passive"))
      (node (ref "R31") (pin "2") (pinfunction "2_2") (pintype "passive"))
      (node (ref "U7") (pin "22") (pinfunction "PD2_22") (pintype "passive"))
    )
    (net (code "37") (name "0V") (class "Default")
      (node (ref "C26") (pin "1") (pinfunction "1_1") (pintype "passive"))
      (node (ref "C27") (pin "2") (pinfunction "2_2") (pintype "passive"))
      (node (ref "C28") (pin "1") (pinfunction "1_1") (pintype "passive"))
      (node (ref "C29") (pin "1") (pinfunction "1_1") (pintype "passive"))
      (node (ref "C30") (pin "1") (pinfunction "1_1") (pintype "passive"))
      (node (ref "C31") (pin "1") (pinfunction "1_1") (pintype "passive"))
      (node (ref "C32") (pin "1") (pinfunction "1_1") (pintype "passive"))
      (node (ref "C33") (pin "1") (pinfunction "1_1") (pintype "passive"))
      (node (ref "C34") (pin "1") (pinfunction "1_1") (pintype "passive"))
      (node (ref "C35") (pin "-") (pinfunction "-_-") (pintype "passive"))
      (node (ref "C36") (pin "1") (pinfunction "1_1") (pintype "passive"))
      (node (ref "C38") (pin "1") (pinfunction "1_1") (pintype "passive"))
      (node (ref "C39") (pin "1") (pinfunction "1_1") (pintype "passive"))
      (node (ref "C40") (pin "2") (pinfunction "2_2") (pintype "passive"))
      (node (ref "C41") (pin "2") (pinfunction "2_2") (pintype "passive"))
      (node (ref "C42") (pin "1") (pinfunction "1_1") (pintype "passive"))
      (node (ref "C43") (pin "1") (pinfunction "1_1") (pintype "passive"))
      (node (ref "C44") (pin "1") (pinfunction "1_1") (pintype "passive"))
      (node (ref "C45") (pin "1") (pinfunction "1_1") (pintype "passive"))
      (node (ref "C46") (pin "1") (pinfunction "1_1") (pintype "passive"))
      (node (ref "C47") (pin "1") (pinfunction "1_1") (pintype "passive"))
      (node (ref "C48") (pin "1") (pinfunction "1_1") (pintype "passive"))
      (node (ref "C49") (pin "2") (pinfunction "2_2") (pintype "passive"))
      (node (ref "C50") (pin "2") (pinfunction "2_2") (pintype "passive"))
      (node (ref "GAIN_SW") (pin "2") (pinfunction "2_2") (pintype "passive"))
      (node (ref "INPUT_SW") (pin "2") (pinfunction "2_2") (pintype "passive"))
      (node (ref "Q11") (pin "E") (pinfunction "E_E") (pintype "passive"))
      (node (ref "Q12") (pin "E") (pinfunction "E_E") (pintype "passive"))
      (node (ref "Q13") (pin "E") (pinfunction "E_E") (pintype "passive"))
      (node (ref "Q14") (pin "E") (pinfunction "E_E") (pintype "passive"))
      (node (ref "Q15") (pin "E") (pinfunction "E_E") (pintype "passive"))
      (node (ref "Q9") (pin "E") (pinfunction "E_E") (pintype "passive"))
      (node (ref "R33") (pin "1") (pinfunction "1_1") (pintype "passive"))
      (node (ref "R34") (pin "1") (pinfunction "1_1") (pintype "passive"))
      (node (ref "R35") (pin "1") (pinfunction "1_1") (pintype "passive"))
      (node (ref "R48") (pin "1") (pinfunction "1_1") (pintype "passive"))
      (node (ref "R59") (pin "1") (pinfunction "1_1") (pintype "passive"))
      (node (ref "U6") (pin "5") (pinfunction "IN2+_5") (pintype "passive"))
      (node (ref "U7") (pin "40") (pinfunction "VSS2_40") (pintype "passive"))
      (node (ref "U7") (pin "9") (pinfunction "VSS1_VSSA_VREF-_9") (pintype "passive"))
      (node (ref "U8") (pin "15") (pinfunction "H4L2_15") (pintype "passive"))
      (node (ref "U8") (pin "9") (pinfunction "GND_9") (pintype "passive"))
      (node (ref "U9") (pin "1") (pinfunction "E0_1") (pintype "passive"))
      (node (ref "U9") (pin "2") (pinfunction "E1_2") (pintype "passive"))
      (node (ref "U9") (pin "3") (pinfunction "E2_3") (pintype "passive"))
      (node (ref "U9") (pin "4") (pinfunction "VSS_4") (pintype "passive"))
    )
    (net (code "38") (name "Net-(C35-Pad+)") (class "Default")
      (node (ref "C35") (pin "+") (pinfunction "+_+") (pintype "passive"))
      (node (ref "R36") (pin "2") (pinfunction "2_2") (pintype "passive"))
      (node (ref "R38") (pin "1") (pinfunction "1_1") (pintype "passive"))
      (node (ref "R39") (pin "1") (pinfunction "1_1") (pintype "passive"))
    )
    (net (code "39") (name "Net-(D19-PadK)") (class "Default")
      (node (ref "D19") (pin "K") (pinfunction "K_K") (pintype "passive"))
      (node (ref "R45") (pin "1") (pinfunction "1_1") (pintype "passive"))
    )
    (net (code "40") (name "Net-(GAIN_SW-Pad1)") (class "Default")
      (node (ref "GAIN_SW") (pin "1") (pinfunction "1_1") (pintype "passive"))
      (node (ref "R46") (pin "2") (pinfunction "2_2") (pintype "passive"))
      (node (ref "R47") (pin "1") (pinfunction "1_1") (pintype "passive"))
    )
    (net (code "41") (name "Net-(GAIN_SW-Pad3)") (class "Default")
      (node (ref "GAIN_SW") (pin "3") (pinfunction "3_3") (pintype "passive"))
      (node (ref "R49") (pin "1") (pinfunction "1_1") (pintype "passive"))
      (node (ref "R50") (pin "1") (pinfunction "1_1") (pintype "passive"))
    )
    (net (code "42") (name "Net-(INPUT_SW-Pad1)") (class "Default")
      (node (ref "INPUT_SW") (pin "1") (pinfunction "1_1") (pintype "passive"))
      (node (ref "R40") (pin "2") (pinfunction "2_2") (pintype "passive"))
      (node (ref "R41") (pin "1") (pinfunction "1_1") (pintype "passive"))
    )
    (net (code "43") (name "Net-(INPUT_SW-Pad3)") (class "Default")
      (node (ref "INPUT_SW") (pin "3") (pinfunction "3_3") (pintype "passive"))
      (node (ref "R42") (pin "1") (pinfunction "1_1") (pintype "passive"))
      (node (ref "R44") (pin "1") (pinfunction "1_1") (pintype "passive"))
    )
    (net (code "44") (name "Net-(Q9-PadB)") (class "Default")
      (node (ref "Q9") (pin "B") (pinfunction "B_B") (pintype "passive"))
      (node (ref "R51") (pin "2") (pinfunction "2_2") (pintype "passive"))
    )
    (net (code "45") (name "Net-(Q10-PadB)") (class "Default")
      (node (ref "Q10") (pin "B") (pinfunction "B_B") (pintype "passive"))
      (node (ref "Q11") (pin "C") (pinfunction "C_C") (pintype "passive"))
      (node (ref "R52") (pin "1") (pinfunction "1_1") (pintype "passive"))
    )
    (net (code "46") (name "Net-(Q11-PadB)") (class "Default")
      (node (ref "Q11") (pin "B") (pinfunction "B_B") (pintype "passive"))
      (node (ref "R56") (pin "2") (pinfunction "2_2") (pintype "passive"))
    )
    (net (code "47") (name "Net-(Q12-PadB)") (class "Default")
      (node (ref "Q12") (pin "B") (pinfunction "B_B") (pintype "passive"))
      (node (ref "R57") (pin "2") (pinfunction "2_2") (pintype "passive"))
    )
    (net (code "48") (name "Net-(Q13-PadB)") (class "Default")
      (node (ref "Q13") (pin "B") (pinfunction "B_B") (pintype "passive"))
      (node (ref "R58") (pin "2") (pinfunction "2_2") (pintype "passive"))
    )
    (net (code "49") (name "Net-(Q14-PadB)") (class "Default")
      (node (ref "Q14") (pin "B") (pinfunction "B_B") (pintype "passive"))
      (node (ref "R60") (pin "2") (pinfunction "2_2") (pintype "passive"))
    )
    (net (code "50") (name "Net-(Q15-PadB)") (class "Default")
      (node (ref "Q15") (pin "B") (pinfunction "B_B") (pintype "passive"))
      (node (ref "R61") (pin "2") (pinfunction "2_2") (pintype "passive"))
    )
    (net (code "51") (name "Net-(U6A-IN1+)") (class "Default")
      (node (ref "D17") (pin "K") (pinfunction "K_K") (pintype "passive"))
      (node (ref "R37") (pin "2") (pinfunction "2_2") (pintype "passive"))
      (node (ref "U6") (pin "3") (pinfunction "IN1+_3") (pintype "passive"))
    )
    (net (code "52") (name "Net-(U6A-IN1-)") (class "Default")
      (node (ref "R30") (pin "1") (pinfunction "1_1") (pintype "passive"))
      (node (ref "U6") (pin "1") (pinfunction "OUT1_1") (pintype "passive"))
      (node (ref "U6") (pin "2") (pinfunction "IN1-_2") (pintype "passive"))
    )
    (net (code "53") (name "Net-(U6B-IN2-)") (class "Default")
      (node (ref "R37") (pin "1") (pinfunction "1_1") (pintype "passive"))
      (node (ref "R38") (pin "2") (pinfunction "2_2") (pintype "passive"))
      (node (ref "U6") (pin "6") (pinfunction "IN2-_6") (pintype "passive"))
    )
    (net (code "54") (name "Net-(U6B-OUT2)") (class "Default")
      (node (ref "D17") (pin "A") (pinfunction "A_A") (pintype "passive"))
      (node (ref "U6") (pin "7") (pinfunction "OUT2_7") (pintype "passive"))
    )
    (net (code "55") (name "Net-(U6C-VCC+)") (class "Default")
      (node (ref "C26") (pin "2") (pinfunction "2_2") (pintype "passive"))
      (node (ref "D15") (pin "K") (pinfunction "K_K") (pintype "passive"))
      (node (ref "U6") (pin "8") (pinfunction "VCC+_8") (pintype "power_in"))
    )
    (net (code "56") (name "Net-(U6C-VCC-)") (class "Default")
      (node (ref "C27") (pin "1") (pinfunction "1_1") (pintype "passive"))
      (node (ref "D18") (pin "A") (pinfunction "A_A") (pintype "passive"))
      (node (ref "U6") (pin "4") (pinfunction "VCC-_4") (pintype "power_in"))
    )
    (net (code "57") (name "Net-(U7A-VLCD)") (class "Default")
      (node (ref "C43") (pin "2") (pinfunction "2_2") (pintype "passive"))
      (node (ref "U7") (pin "13") (pinfunction "VLCD_13") (pintype "passive"))
    )
    (net (code "58") (name "Net-(U7A-~{RS}T_PA1)") (class "Default")
      (node (ref "C37") (pin "2") (pinfunction "2_2") (pintype "passive"))
      (node (ref "R43") (pin "1") (pinfunction "1_1") (pintype "passive"))
      (node (ref "U7") (pin "2") (pinfunction "~{RS}T_PA1_2") (pintype "passive"))
    )
    (net (code "59") (name "Net-(U7F-PE0)") (class "Default")
      (node (ref "R45") (pin "2") (pinfunction "2_2") (pintype "passive"))
      (node (ref "U7") (pin "14") (pinfunction "PE0_14") (pintype "passive"))
    )
    (net (code "60") (name "Net-(U8-ID0)") (class "Default")
      (node (ref "R59") (pin "2") (pinfunction "2_2") (pintype "passive"))
      (node (ref "U8") (pin "19") (pinfunction "ID0_19") (pintype "passive"))
    )
    (net (code "61") (name "Net-(U8-XI)") (class "Default")
      (node (ref "C49") (pin "1") (pinfunction "1_1") (pintype "passive"))
      (node (ref "U10") (pin "1") (pinfunction "1_1") (pintype "passive"))
      (node (ref "U8") (pin "10") (pinfunction "XI_10") (pintype "passive"))
    )
    (net (code "62") (name "Net-(U8-XO)") (class "Default")
      (node (ref "C50") (pin "1") (pinfunction "1_1") (pintype "passive"))
      (node (ref "U10") (pin "2") (pinfunction "2_2") (pintype "passive"))
      (node (ref "U8") (pin "11") (pinfunction "XO_11") (pintype "passive"))
    )
    (net (code "63") (name "VBUS") (class "Default")
      (node (ref "R29") (pin "2") (pinfunction "2_2") (pintype "passive"))
    )
    (net (code "64") (name "unconnected-(U7B-PA0-Pad1)") (class "Default")
      (node (ref "U7") (pin "1") (pinfunction "PA0_1") (pintype "passive"))
    )
    (net (code "65") (name "unconnected-(U7B-PA2-Pad3)") (class "Default")
      (node (ref "U7") (pin "3") (pinfunction "PA2_3") (pintype "passive"))
    )
    (net (code "66") (name "unconnected-(U7B-PA3-Pad4)") (class "Default")
      (node (ref "U7") (pin "4") (pinfunction "PA3_4") (pintype "passive"))
    )
    (net (code "67") (name "unconnected-(U7C-PB0-Pad24)") (class "Default")
      (node (ref "U7") (pin "24") (pinfunction "PB0_24") (pintype "passive"))
    )
    (net (code "68") (name "unconnected-(U7C-PB1-Pad25)") (class "Default")
      (node (ref "U7") (pin "25") (pinfunction "PB1_25") (pintype "passive"))
    )
    (net (code "69") (name "unconnected-(U7C-PB3-Pad27)") (class "Default")
      (node (ref "U7") (pin "27") (pinfunction "PB3_27") (pintype "passive"))
    )
    (net (code "70") (name "unconnected-(U7C-PB4-Pad28)") (class "Default")
      (node (ref "U7") (pin "28") (pinfunction "PB4_28") (pintype "passive"))
    )
    (net (code "71") (name "unconnected-(U7C-PB5-Pad29)") (class "Default")
      (node (ref "U7") (pin "29") (pinfunction "PB5_29") (pintype "passive"))
    )
    (net (code "72") (name "unconnected-(U7D-PC0-Pad37)") (class "Default")
      (node (ref "U7") (pin "37") (pinfunction "PC0_37") (pintype "passive"))
    )
    (net (code "73") (name "unconnected-(U7D-PC1-Pad38)") (class "Default")
      (node (ref "U7") (pin "38") (pinfunction "PC1_38") (pintype "passive"))
    )
    (net (code "74") (name "unconnected-(U7D-PC2-Pad41)") (class "Default")
      (node (ref "U7") (pin "41") (pinfunction "PC2_41") (pintype "passive"))
    )
    (net (code "75") (name "unconnected-(U7D-PC4-Pad43)") (class "Default")
      (node (ref "U7") (pin "43") (pinfunction "PC4_43") (pintype "passive"))
    )
    (net (code "76") (name "unconnected-(U7D-PC5-Pad44)") (class "Default")
      (node (ref "U7") (pin "44") (pinfunction "PC5_44") (pintype "passive"))
    )
    (net (code "77") (name "unconnected-(U7D-PC6-Pad45)") (class "Default")
      (node (ref "U7") (pin "45") (pinfunction "PC6_45") (pintype "passive"))
    )
    (net (code "78") (name "unconnected-(U7D-PC7-Pad46)") (class "Default")
      (node (ref "U7") (pin "46") (pinfunction "PC7_46") (pintype "passive"))
    )
    (net (code "79") (name "unconnected-(U7F-PE5-Pad19)") (class "Default")
      (node (ref "U7") (pin "19") (pinfunction "PE5_19") (pintype "passive"))
    )
    (net (code "80") (name "unconnected-(U7F-PE6-Pad47)") (class "Default")
      (node (ref "U7") (pin "47") (pinfunction "PE6_47") (pintype "passive"))
    )
    (net (code "81") (name "unconnected-(U7F-PE7-Pad48)") (class "Default")
      (node (ref "U7") (pin "48") (pinfunction "PE7_48") (pintype "passive"))
    )
    (net (code "82") (name "unconnected-(U8-ID1-Pad13)") (class "Default")
      (node (ref "U8") (pin "13") (pinfunction "ID1_13") (pintype "passive+no_connect"))
    )
    (net (code "83") (name "unconnected-(U8-NC-Pad3)") (class "Default")
      (node (ref "U8") (pin "3") (pinfunction "NC_3") (pintype "passive+no_connect"))
    )
    (net (code "84") (name "unconnected-(U8-RDY-Pad4)") (class "Default")
      (node (ref "U8") (pin "4") (pinfunction "RDY_4") (pintype "passive+no_connect"))
    )
    (net (code "85") (name "unconnected-(U8-SCLK-Pad2)") (class "Default")
      (node (ref "U8") (pin "2") (pinfunction "SCLK_2") (pintype "passive+no_connect"))
    )
    (net (code "86") (name "unconnected-(U8-SIN-Pad14)") (class "Default")
      (node (ref "U8") (pin "14") (pinfunction "SIN_14") (pintype "passive+no_connect"))
    )
    (net (code "87") (name "unconnected-(U8-SOUT-Pad1)") (class "Default")
      (node (ref "U8") (pin "1") (pinfunction "SOUT_1") (pintype "passive+no_connect"))
    )
    (net (code "88") (name "unconnected-(U8-UD+-Pad7)") (class "Default")
      (node (ref "U8") (pin "7") (pinfunction "UD+_7") (pintype "passive"))
    )
    (net (code "89") (name "unconnected-(U8-UD--Pad8)") (class "Default")
      (node (ref "U8") (pin "8") (pinfunction "UD-_8") (pintype "passive"))
    )
    (net (code "90") (name "unconnected-(U8-WP#-Pad5)") (class "Default")
      (node (ref "U8") (pin "5") (pinfunction "WP#_5") (pintype "passive+no_connect"))
    )
  )
)
